# eBox_Wifi.net
KiCad netlist of a schematic drawn in Altium Designer
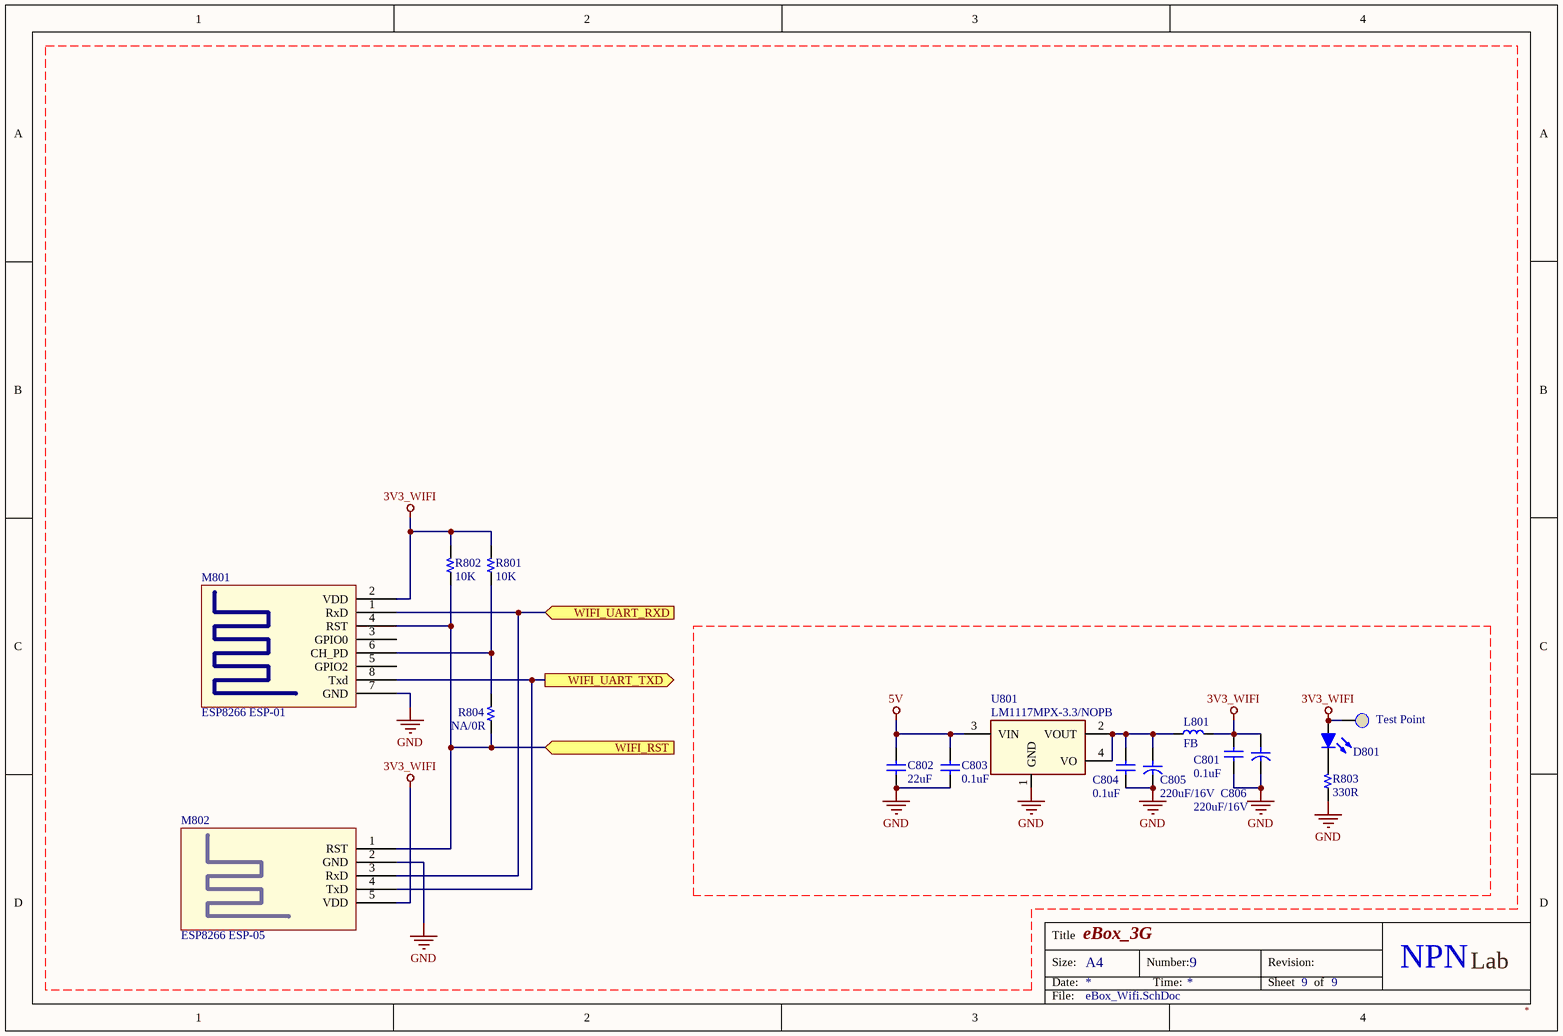
[diagram p0: eBox_Wifi.SchDoc]

(export (version "E")
  (design (tool "Eeschema 10.0.6"))
  (components
    (comp (ref "3V3WiFi")
      (value "Test Point")
      (footprint "TestPoint/SMD/1.5mm")
      (libsource (lib "chipfc_altium_libs") (part "Test Point"))
    )
    (comp (ref "C801")
      (value "0.1uF")
      (footprint "C 0805")
      (description "CAP CER 0.1UF 50V X7R 0805")
      (libsource (lib "chipfc_altium_libs") (part "Capacitor NP"))
    )
    (comp (ref "C802")
      (value "22uF")
      (footprint "C 1210 mix 0805")
      (description "CAP CER 22UF 10% 16V X7R 1210")
      (libsource (lib "chipfc_altium_libs") (part "Capacitor NP"))
    )
    (comp (ref "C803")
      (value "0.1uF")
      (footprint "C 0805")
      (description "CAP CER 0.1UF 50V X7R 0805")
      (libsource (lib "chipfc_altium_libs") (part "Capacitor NP"))
    )
    (comp (ref "C804")
      (value "0.1uF")
      (footprint "C 0805")
      (description "CAP CER 0.1UF 50V X7R 0805")
      (libsource (lib "chipfc_altium_libs") (part "Capacitor NP"))
    )
    (comp (ref "C805")
      (value "220uF/16V")
      (footprint "CYL/D.250/LS.100-D63H70P25")
      (description "CAP ALUM 220UF 20% 16V RADIAL")
      (libsource (lib "chipfc_altium_libs") (part "Capacitor"))
    )
    (comp (ref "C806")
      (value "220uF/16V")
      (footprint "CYL/D.250/LS.100-D63H70P25")
      (description "CAP ALUM 220UF 20% 16V RADIAL")
      (libsource (lib "chipfc_altium_libs") (part "Capacitor"))
    )
    (comp (ref "D801")
      (value "LED RED 3MM")
      (footprint "LED 3MM - red")
      (description "LED RED DIFFUSED 3MM ROUND T/H")
      (libsource (lib "chipfc_altium_libs") (part "Led"))
    )
    (comp (ref "L801")
      (value "FB")
      (footprint "L 0805 (2012)")
      (description "Chip Ferrite Bead")
      (libsource (lib "chipfc_altium_libs") (part "Inductor"))
    )
    (comp (ref "M801")
      (value "ESP8266 ESP-01")
      (footprint "ESP8266 ESP-01")
      (libsource (lib "ESP8266") (part "ESP8266 ESP-01"))
    )
    (comp (ref "M802")
      (value "ESP8266 ESP-05")
      (footprint "ESP8266 ESP-05")
      (libsource (lib "ESP8266") (part "ESP8266 ESP-05"))
    )
    (comp (ref "R801")
      (value "10K")
      (footprint "R 0603")
      (description "RES SMD 10K OHM 1% 1/10W 0603")
      (libsource (lib "common_altium_libs") (part "Resistor"))
    )
    (comp (ref "R802")
      (value "10K")
      (footprint "R 0603")
      (description "RES SMD 10K OHM 1% 1/10W 0603")
      (libsource (lib "common_altium_libs") (part "Resistor"))
    )
    (comp (ref "R803")
      (value "330R")
      (footprint "R 0603")
      (description "RES SMD 330 OHM 1% 1/10W 0603")
      (libsource (lib "chipfc_altium_libs") (part "Resistor"))
    )
    (comp (ref "R804")
      (value "NA/0R")
      (footprint "R 0603")
      (description "RES SMD 0 OHM 1% 1/10W 0603")
      (libsource (lib "chipfc_altium_libs") (part "Resistor"))
    )
    (comp (ref "U801")
      (value "LM1117MPX-3.3/NOPB")
      (footprint "SOT-223")
      (description "IC REG LINEAR 3.3V 800MA SOT223")
      (libsource (lib "chipfc_altium_libs") (part "AMS1117"))
    )
  )
  (nets
    (net (code "1") (name "/WIFI_RST") (class "Default")
      (node (ref "M801") (pin "4") (pinfunction "RST_4") (pintype "passive"))
      (node (ref "M802") (pin "1") (pinfunction "RST_1") (pintype "passive"))
      (node (ref "R802") (pin "1") (pinfunction "1_1") (pintype "passive"))
      (node (ref "R804") (pin "1") (pinfunction "1_1") (pintype "passive"))
    )
    (net (code "2") (name "/WIFI_UART_RXD") (class "Default")
      (node (ref "M801") (pin "1") (pinfunction "RxD_1") (pintype "passive"))
      (node (ref "M802") (pin "3") (pinfunction "RxD_3") (pintype "passive"))
    )
    (net (code "3") (name "/WIFI_UART_TXD") (class "Default")
      (node (ref "M801") (pin "8") (pinfunction "Txd_8") (pintype "passive"))
      (node (ref "M802") (pin "4") (pinfunction "TxD_4") (pintype "passive"))
    )
    (net (code "4") (name "3V3_WIFI") (class "Default")
      (node (ref "3V3WiFi") (pin "1") (pinfunction "TP_1") (pintype "passive"))
      (node (ref "C801") (pin "1") (pinfunction "1_1") (pintype "passive"))
      (node (ref "C806") (pin "1") (pinfunction "1_1") (pintype "passive"))
      (node (ref "D801") (pin "1") (pinfunction "A_1") (pintype "passive"))
      (node (ref "L801") (pin "2") (pinfunction "2_2") (pintype "passive"))
      (node (ref "M801") (pin "2") (pinfunction "VDD_2") (pintype "passive"))
      (node (ref "M802") (pin "5") (pinfunction "VDD_5") (pintype "passive"))
      (node (ref "R801") (pin "2") (pinfunction "2_2") (pintype "passive"))
      (node (ref "R802") (pin "2") (pinfunction "2_2") (pintype "passive"))
    )
    (net (code "5") (name "5V") (class "Default")
      (node (ref "C802") (pin "1") (pinfunction "1_1") (pintype "passive"))
      (node (ref "C803") (pin "1") (pinfunction "1_1") (pintype "passive"))
      (node (ref "U801") (pin "3") (pinfunction "VIN_3") (pintype "power_in"))
    )
    (net (code "6") (name "GND") (class "Default")
      (node (ref "C801") (pin "2") (pinfunction "2_2") (pintype "passive"))
      (node (ref "C802") (pin "2") (pinfunction "2_2") (pintype "passive"))
      (node (ref "C803") (pin "2") (pinfunction "2_2") (pintype "passive"))
      (node (ref "C804") (pin "2") (pinfunction "2_2") (pintype "passive"))
      (node (ref "C805") (pin "2") (pinfunction "2_2") (pintype "passive"))
      (node (ref "C806") (pin "2") (pinfunction "2_2") (pintype "passive"))
      (node (ref "M801") (pin "7") (pinfunction "GND_7") (pintype "passive"))
      (node (ref "M802") (pin "2") (pinfunction "GND_2") (pintype "passive"))
      (node (ref "R803") (pin "1") (pinfunction "1_1") (pintype "passive"))
      (node (ref "U801") (pin "1") (pinfunction "GND_1") (pintype "passive"))
    )
    (net (code "7") (name "Net-(D801-K)") (class "Default")
      (node (ref "D801") (pin "2") (pinfunction "K_2") (pintype "passive"))
      (node (ref "R803") (pin "2") (pinfunction "2_2") (pintype "passive"))
    )
    (net (code "8") (name "Net-(M801-CH_PD)") (class "Default")
      (node (ref "M801") (pin "6") (pinfunction "CH_PD_6") (pintype "passive"))
      (node (ref "R801") (pin "1") (pinfunction "1_1") (pintype "passive"))
      (node (ref "R804") (pin "2") (pinfunction "2_2") (pintype "passive"))
    )
    (net (code "9") (name "Net-(U801-VO)") (class "Default")
      (node (ref "C804") (pin "1") (pinfunction "1_1") (pintype "passive"))
      (node (ref "C805") (pin "1") (pinfunction "1_1") (pintype "passive"))
      (node (ref "L801") (pin "1") (pinfunction "1_1") (pintype "passive"))
      (node (ref "U801") (pin "2") (pinfunction "VOUT_2") (pintype "passive"))
      (node (ref "U801") (pin "4") (pinfunction "VO_4") (pintype "passive"))
    )
    (net (code "10") (name "unconnected-(M801-GPIO0-Pad3)") (class "Default")
      (node (ref "M801") (pin "3") (pinfunction "GPIO0_3") (pintype "passive"))
    )
    (net (code "11") (name "unconnected-(M801-GPIO2-Pad5)") (class "Default")
      (node (ref "M801") (pin "5") (pinfunction "GPIO2_5") (pintype "passive"))
    )
  )
)
